# IMX477_MIPI_HDMI.net
KiCad netlist of a schematic drawn in Altium Designer
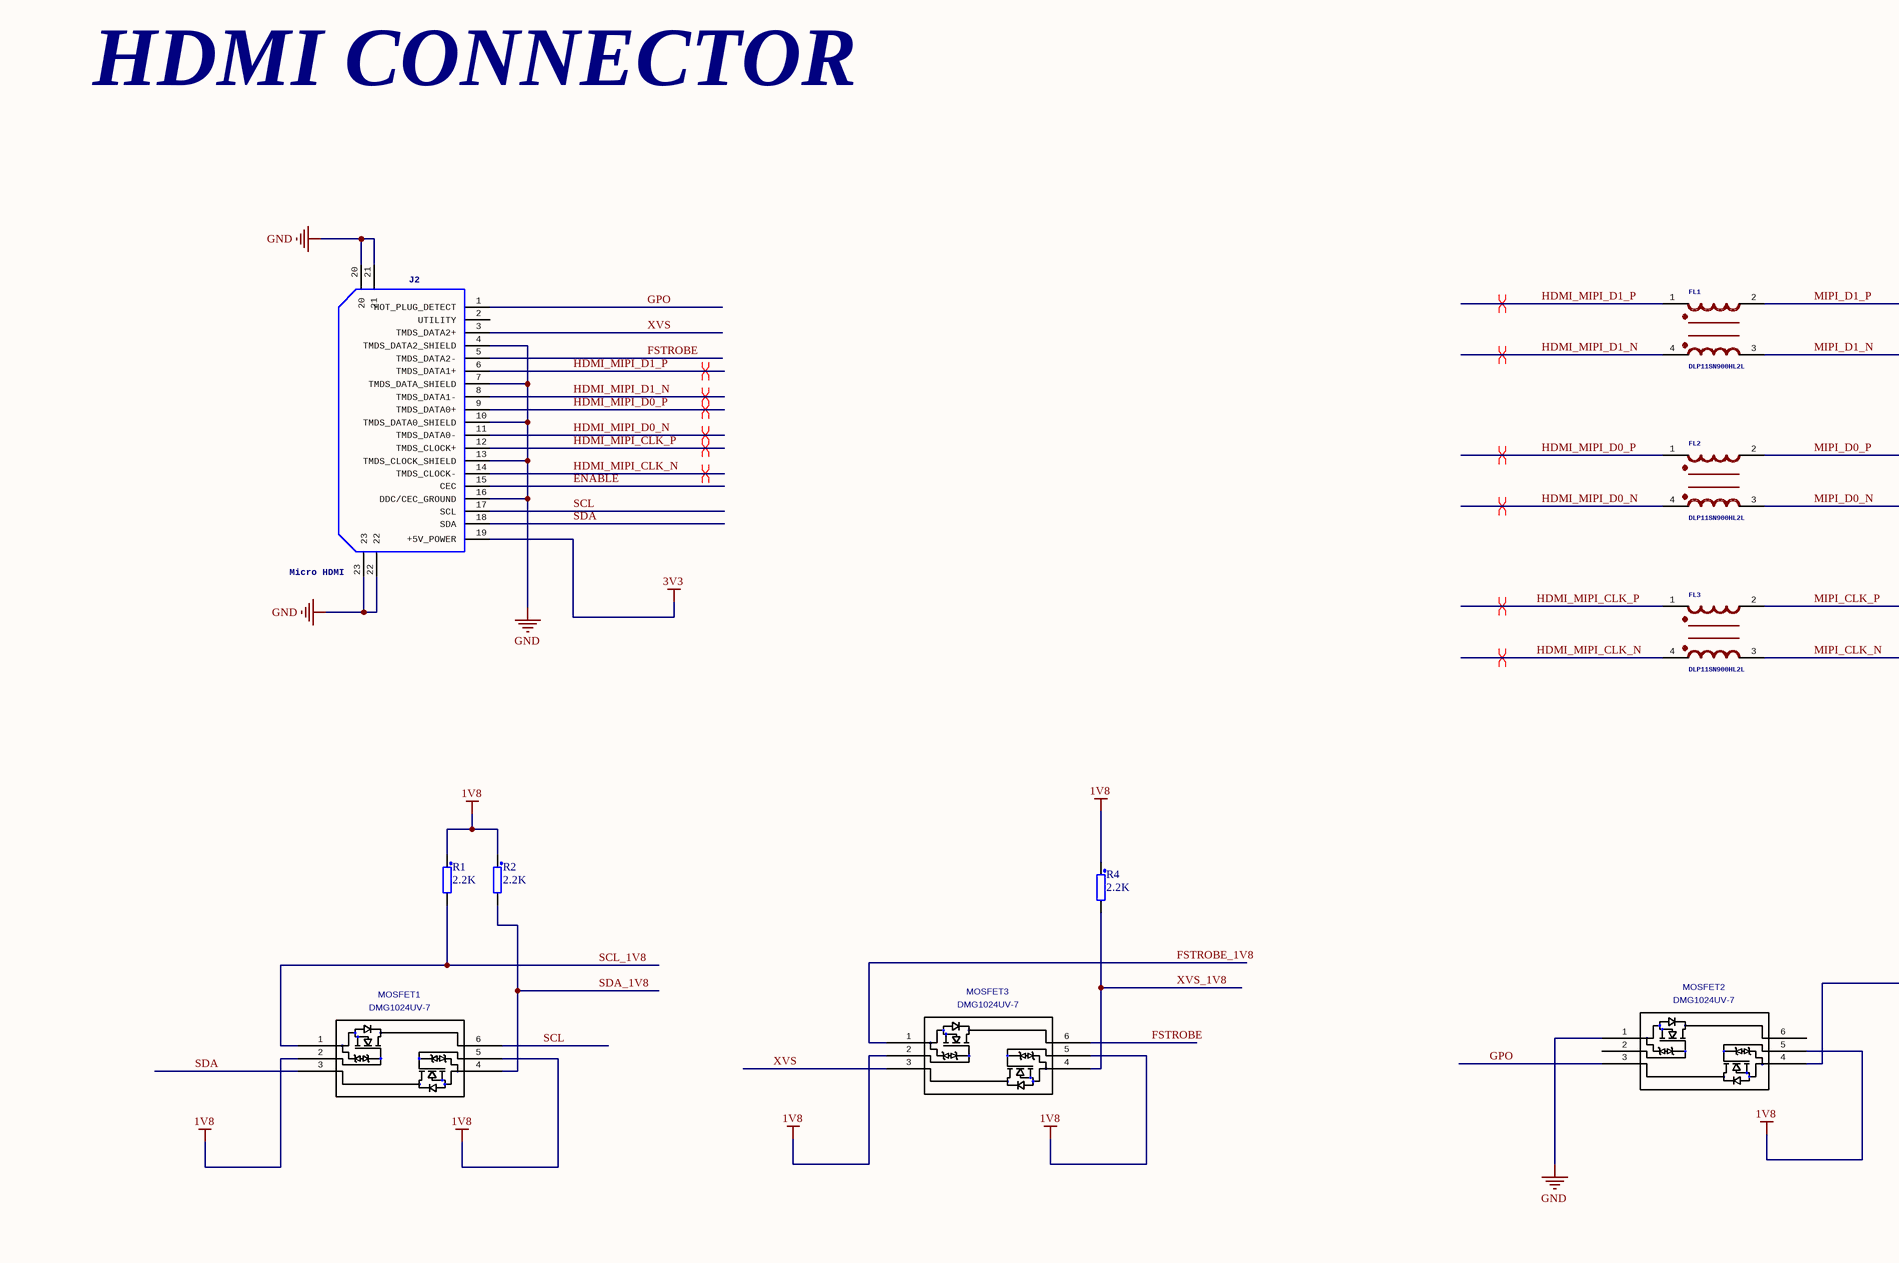
[diagram p0: IMX477_MIPI_HDMI.SchDoc, top left]
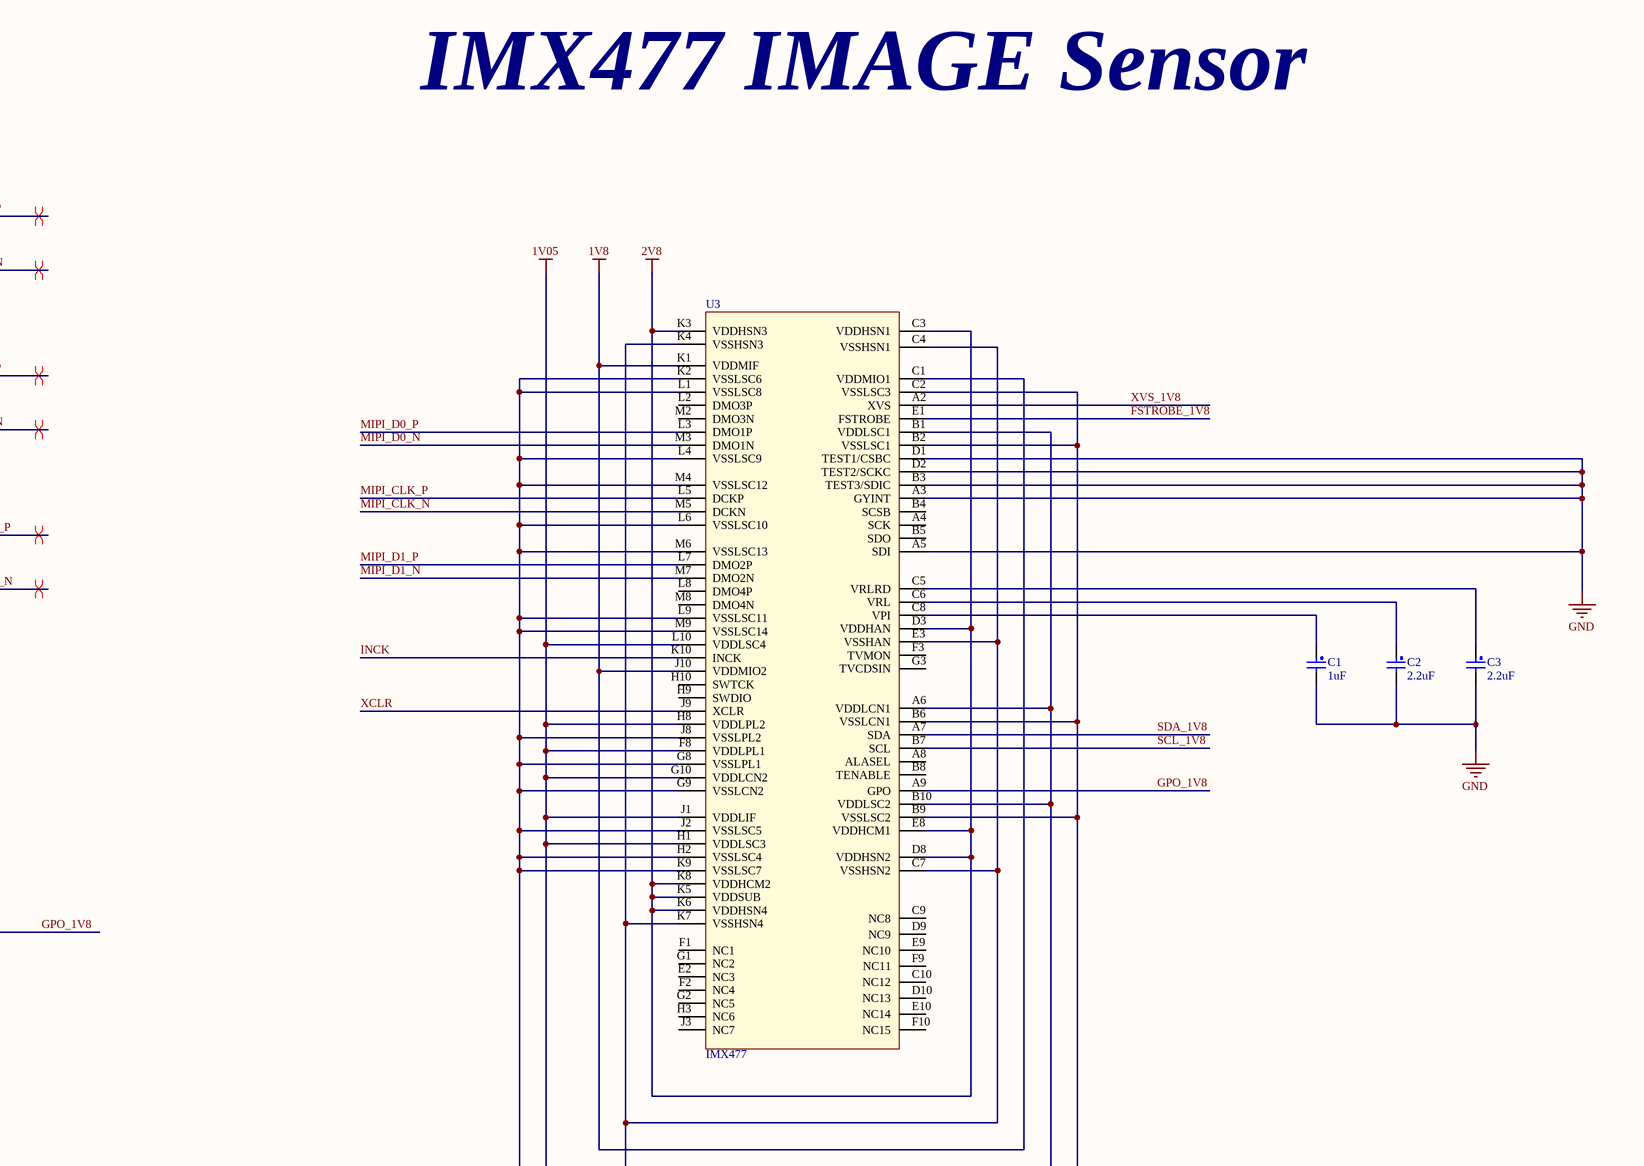
[diagram p1: IMX477_MIPI_HDMI.SchDoc, top right]
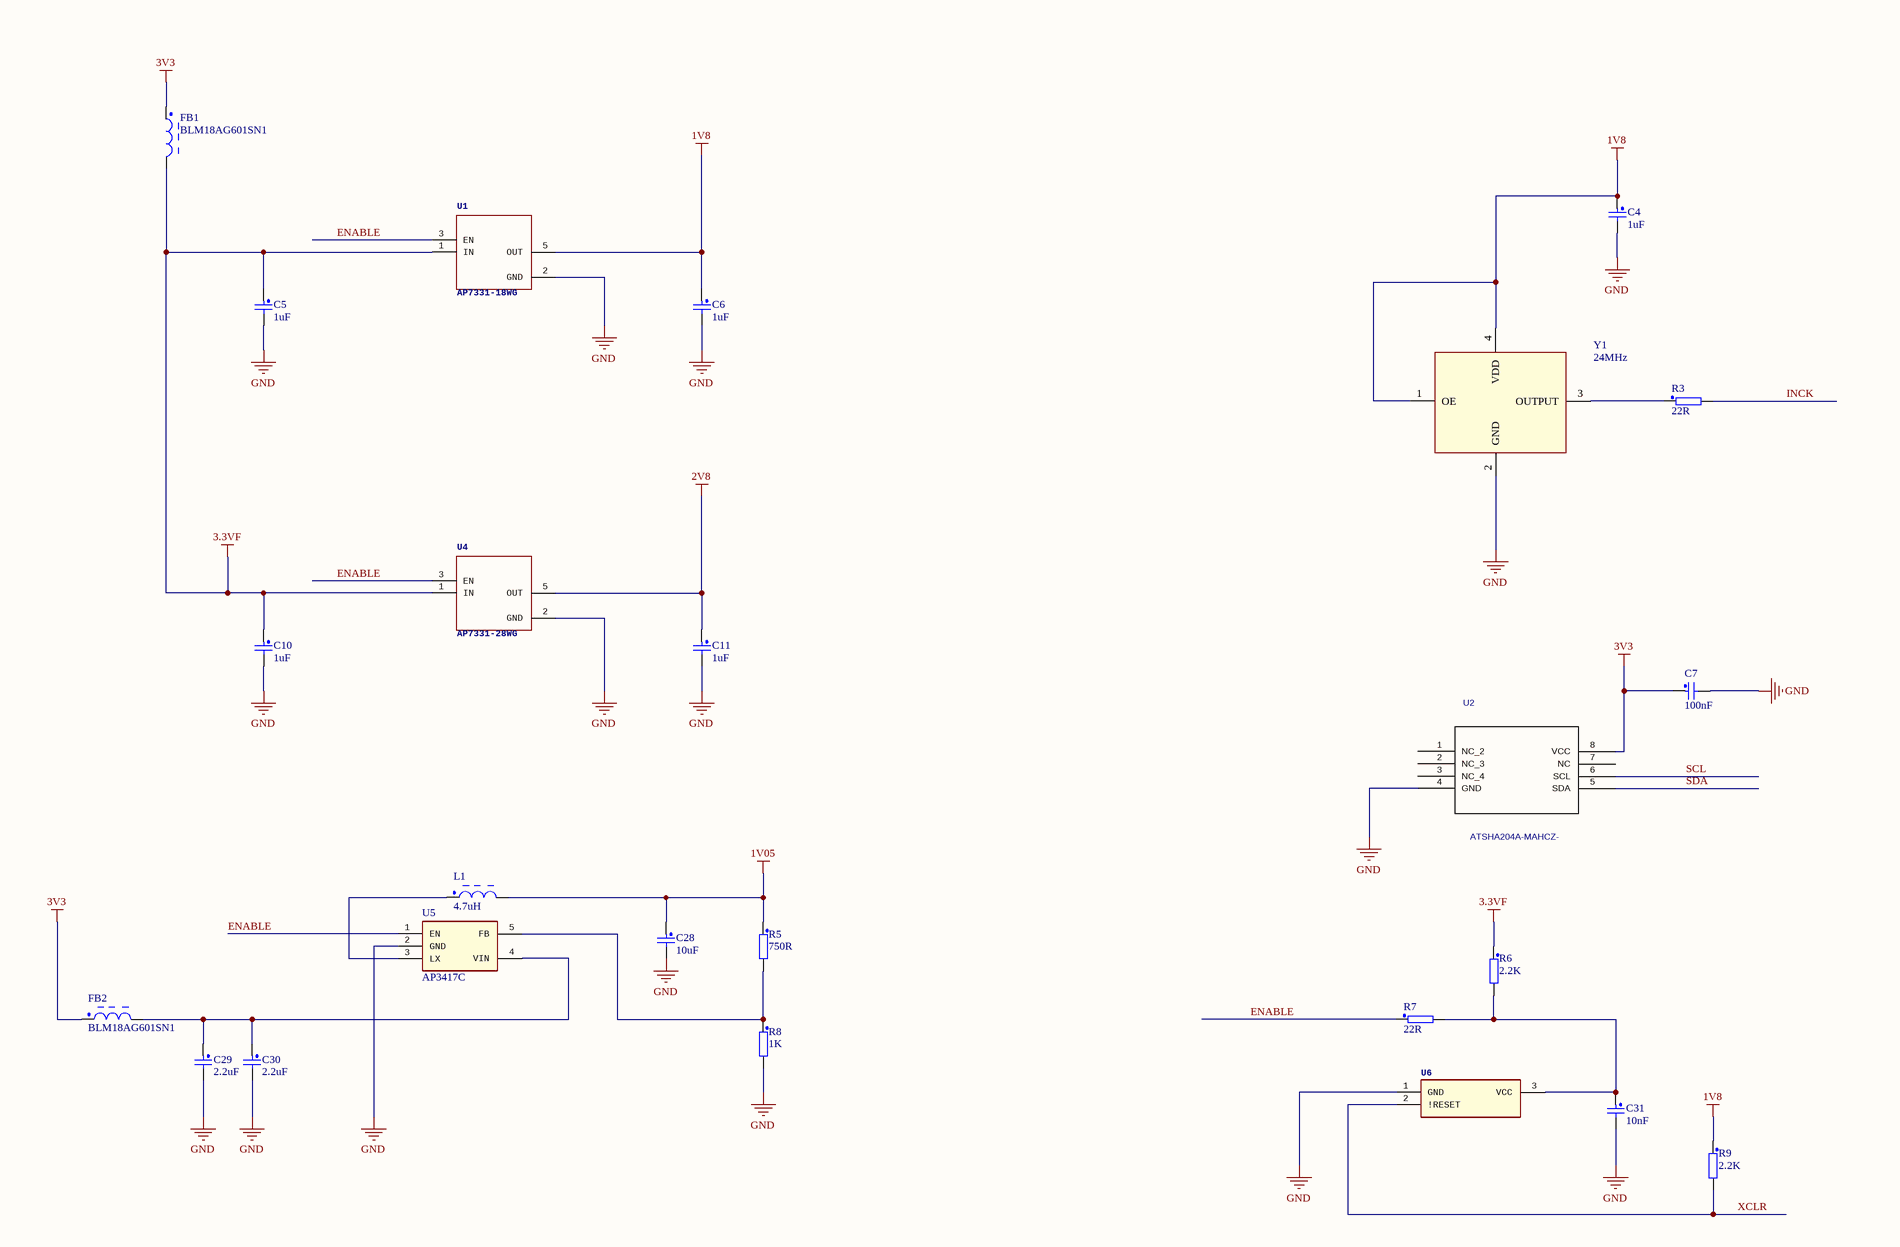
[diagram p2: IMX477_MIPI_HDMI.SchDoc, bottom left]
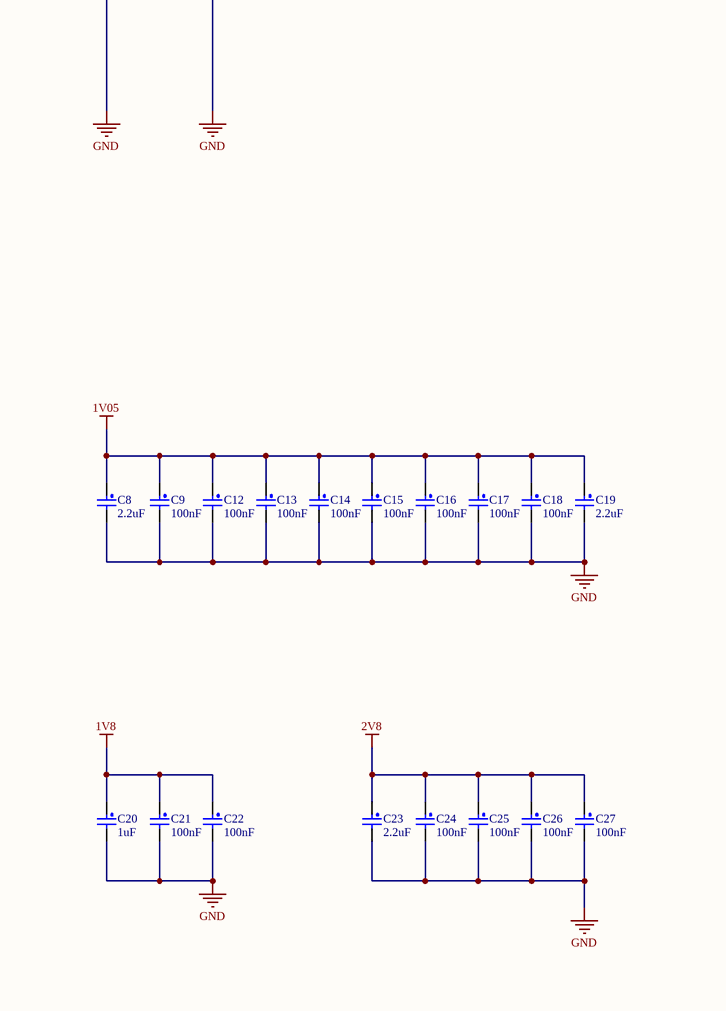
[diagram p3: IMX477_MIPI_HDMI.SchDoc, bottom right]

(export (version "E")
  (design (tool "Eeschema 10.0.6"))
  (components
    (comp (ref "C1")
      (value "1uF")
      (footprint "CAP-0402")
      (description "Capacitor")
      (libsource (lib "TASK-3DLIB") (part "CAP"))
    )
    (comp (ref "C2")
      (value "2.2uF")
      (footprint "CAP-0603")
      (description "Capacitor")
      (libsource (lib "TASK-3DLIB") (part "CAP"))
    )
    (comp (ref "C3")
      (value "2.2uF")
      (footprint "CAP-0603")
      (description "Capacitor")
      (libsource (lib "TASK-3DLIB") (part "CAP"))
    )
    (comp (ref "C4")
      (value "1uF")
      (footprint "CAP-0402")
      (description "Capacitor")
      (libsource (lib "TASK-3DLIB") (part "CAP"))
    )
    (comp (ref "C5")
      (value "1uF")
      (footprint "CAP-0402")
      (description "Capacitor")
      (libsource (lib "TASK-3DLIB") (part "CAP"))
    )
    (comp (ref "C6")
      (value "1uF")
      (footprint "CAP-0402")
      (description "Capacitor")
      (libsource (lib "TASK-3DLIB") (part "CAP"))
    )
    (comp (ref "C7")
      (value "100nF")
      (footprint "CAP-0402")
      (description "Capacitor")
      (libsource (lib "TASK-3DLIB") (part "CAP"))
    )
    (comp (ref "C8")
      (value "2.2uF")
      (footprint "CAP-0603")
      (description "Capacitor")
      (libsource (lib "TASK-3DLIB") (part "CAP"))
    )
    (comp (ref "C9")
      (value "100nF")
      (footprint "CAP-0402")
      (description "Capacitor")
      (libsource (lib "TASK-3DLIB") (part "CAP"))
    )
    (comp (ref "C10")
      (value "1uF")
      (footprint "CAP-0402")
      (description "Capacitor")
      (libsource (lib "TASK-3DLIB") (part "CAP"))
    )
    (comp (ref "C11")
      (value "1uF")
      (footprint "CAP-0402")
      (description "Capacitor")
      (libsource (lib "TASK-3DLIB") (part "CAP"))
    )
    (comp (ref "C12")
      (value "100nF")
      (footprint "CAP-0402")
      (description "Capacitor")
      (libsource (lib "TASK-3DLIB") (part "CAP"))
    )
    (comp (ref "C13")
      (value "100nF")
      (footprint "CAP-0402")
      (description "Capacitor")
      (libsource (lib "TASK-3DLIB") (part "CAP"))
    )
    (comp (ref "C14")
      (value "100nF")
      (footprint "CAP-0402")
      (description "Capacitor")
      (libsource (lib "TASK-3DLIB") (part "CAP"))
    )
    (comp (ref "C15")
      (value "100nF")
      (footprint "CAP-0402")
      (description "Capacitor")
      (libsource (lib "TASK-3DLIB") (part "CAP"))
    )
    (comp (ref "C16")
      (value "100nF")
      (footprint "CAP-0402")
      (description "Capacitor")
      (libsource (lib "TASK-3DLIB") (part "CAP"))
    )
    (comp (ref "C17")
      (value "100nF")
      (footprint "CAP-0402")
      (description "Capacitor")
      (libsource (lib "TASK-3DLIB") (part "CAP"))
    )
    (comp (ref "C18")
      (value "100nF")
      (footprint "CAP-0402")
      (description "Capacitor")
      (libsource (lib "TASK-3DLIB") (part "CAP"))
    )
    (comp (ref "C19")
      (value "2.2uF")
      (footprint "CAP-0603")
      (description "Capacitor")
      (libsource (lib "TASK-3DLIB") (part "CAP"))
    )
    (comp (ref "C20")
      (value "1uF")
      (footprint "CAP-0402")
      (description "Capacitor")
      (libsource (lib "TASK-3DLIB") (part "CAP"))
    )
    (comp (ref "C21")
      (value "100nF")
      (footprint "CAP-0402")
      (description "Capacitor")
      (libsource (lib "TASK-3DLIB") (part "CAP"))
    )
    (comp (ref "C22")
      (value "100nF")
      (footprint "CAP-0402")
      (description "Capacitor")
      (libsource (lib "TASK-3DLIB") (part "CAP"))
    )
    (comp (ref "C23")
      (value "2.2uF")
      (footprint "CAP-0603")
      (description "Capacitor")
      (libsource (lib "TASK-3DLIB") (part "CAP"))
    )
    (comp (ref "C24")
      (value "100nF")
      (footprint "CAP-0402")
      (description "Capacitor")
      (libsource (lib "TASK-3DLIB") (part "CAP"))
    )
    (comp (ref "C25")
      (value "100nF")
      (footprint "CAP-0402")
      (description "Capacitor")
      (libsource (lib "TASK-3DLIB") (part "CAP"))
    )
    (comp (ref "C26")
      (value "100nF")
      (footprint "CAP-0402")
      (description "Capacitor")
      (libsource (lib "TASK-3DLIB") (part "CAP"))
    )
    (comp (ref "C27")
      (value "100nF")
      (footprint "CAP-0402")
      (description "Capacitor")
      (libsource (lib "TASK-3DLIB") (part "CAP"))
    )
    (comp (ref "C28")
      (value "10uF")
      (footprint "CAP-0805-S")
      (description "Capacitor")
      (libsource (lib "TASK-3DLIB") (part "CAP"))
    )
    (comp (ref "C29")
      (value "2.2uF")
      (footprint "CAP-0603")
      (description "Capacitor")
      (libsource (lib "TASK-3DLIB") (part "CAP"))
    )
    (comp (ref "C30")
      (value "2.2uF")
      (footprint "CAP-0603")
      (description "Capacitor")
      (libsource (lib "TASK-3DLIB") (part "CAP"))
    )
    (comp (ref "C31")
      (value "10nF")
      (footprint "CAP-0402")
      (description "Capacitor")
      (libsource (lib "TASK-3DLIB") (part "CAP"))
    )
    (comp (ref "FB1")
      (value "BLM18AG601SN1")
      (footprint "FBD-0603-S")
      (description "Inductor")
      (libsource (lib "TASK-3DLIB") (part "INDUCTOR"))
    )
    (comp (ref "FB2")
      (value "BLM18AG601SN1")
      (footprint "FBD-0603-S")
      (description "Inductor")
      (libsource (lib "TASK-3DLIB") (part "INDUCTOR"))
    )
    (comp (ref "FL1")
      (value "DLP11SN900HL2L")
      (footprint "DLP11SN900HL2L")
      (fields (field (name "MF") "Murata") (field (name "DIGI-KEY_PART_NUMBER") "490-5143-1-ND"))
      (libsource (lib "TASK-3DLIB") (part "DLP11SN900HL2L"))
    )
    (comp (ref "FL2")
      (value "DLP11SN900HL2L")
      (footprint "DLP11SN900HL2L")
      (fields (field (name "MF") "Murata") (field (name "DIGI-KEY_PART_NUMBER") "490-5143-1-ND"))
      (libsource (lib "TASK-3DLIB") (part "DLP11SN900HL2L"))
    )
    (comp (ref "FL3")
      (value "DLP11SN900HL2L")
      (footprint "DLP11SN900HL2L")
      (fields (field (name "MF") "Murata") (field (name "DIGI-KEY_PART_NUMBER") "490-5143-1-ND"))
      (libsource (lib "TASK-3DLIB") (part "DLP11SN900HL2L"))
    )
    (comp (ref "J2")
      (value "Micro HDMI")
      (footprint "HDMI-0467650301")
      (fields (field (name "MANUFACTURER_PART_NUMBER") "0467650301"))
      (libsource (lib "TASK-3DLIB") (part "HDMI-0467650301"))
    )
    (comp (ref "L1")
      (value "4.7uH")
      (footprint "IND-1008")
      (description "Inductor")
      (libsource (lib "TASK-3DLIB") (part "INDUCTOR"))
    )
    (comp (ref "MOSFET1")
      (value "DMG1024UV-7")
      (footprint "SOT-563_DIO")
      (fields (field (name "COPYRIGHT") "Copyright (C) 2018 Accelerated Designs. All rights reserved"))
      (libsource (lib "TASK-3DLIB") (part "DMG1024UV-7"))
    )
    (comp (ref "MOSFET2")
      (value "DMG1024UV-7")
      (footprint "SOT-563_DIO")
      (fields (field (name "COPYRIGHT") "Copyright (C) 2018 Accelerated Designs. All rights reserved"))
      (libsource (lib "TASK-3DLIB") (part "DMG1024UV-7"))
    )
    (comp (ref "MOSFET3")
      (value "DMG1024UV-7")
      (footprint "SOT-563_DIO")
      (fields (field (name "COPYRIGHT") "Copyright (C) 2018 Accelerated Designs. All rights reserved"))
      (libsource (lib "TASK-3DLIB") (part "DMG1024UV-7"))
    )
    (comp (ref "R1") (value "2.2K") (footprint "RES-0402") (libsource (lib "TASK-3DLIB") (part "RES")))
    (comp (ref "R2") (value "2.2K") (footprint "RES-0402") (libsource (lib "TASK-3DLIB") (part "RES")))
    (comp (ref "R3") (value "22R") (footprint "RES-0402") (libsource (lib "TASK-3DLIB") (part "RES")))
    (comp (ref "R4") (value "2.2K") (footprint "RES-0402") (libsource (lib "TASK-3DLIB") (part "RES")))
    (comp (ref "R5") (value "750R") (footprint "RES-0402") (libsource (lib "TASK-3DLIB") (part "RES")))
    (comp (ref "R6") (value "2.2K") (footprint "RES-0402") (libsource (lib "TASK-3DLIB") (part "RES")))
    (comp (ref "R7") (value "22R") (footprint "RES-0402") (libsource (lib "TASK-3DLIB") (part "RES")))
    (comp (ref "R8") (value "1K") (footprint "RES-0402") (libsource (lib "TASK-3DLIB") (part "RES")))
    (comp (ref "R9") (value "2.2K") (footprint "RES-0402") (libsource (lib "TASK-3DLIB") (part "RES")))
    (comp (ref "U1")
      (value "AP7331-18WG")
      (footprint "AP7331-sot-25")
      (fields
        (field (name "MP") "AP7331-18WG-7")
        (field (name "MF") "Diodes Inc.")
        (field (name "DIGI-KEY_PART_NUMBER") "AP7331-18WG-7DICT-ND")
      )
      (libsource (lib "TASK-3DLIB") (part "AP7331-xxWG-7"))
    )
    (comp (ref "U2")
      (value "ATSHA204A-MAHCZ-")
      (footprint "ATSHA204A")
      (fields
        (field (name "MANUFACTURER_PART_NUMBER") "ATSHA204A-MAHCZ-T")
        (field (name "COPYRIGHT") "Copyright (C) 2018 Accelerated Designs. All rights reserved")
      )
      (libsource (lib "TASK-3DLIB") (part "ATSHA204A-MAHCZ-"))
    )
    (comp (ref "U3") (value "IMX477") (footprint "IMX477") (libsource (lib "TASK-3DLIB") (part "IMX477")))
    (comp (ref "U4")
      (value "AP7331-28WG")
      (footprint "AP7331-sot-25")
      (fields
        (field (name "MP") "AP7331-18WG-7")
        (field (name "MF") "Diodes Inc.")
        (field (name "DIGI-KEY_PART_NUMBER") "AP7331-18WG-7DICT-ND")
      )
      (libsource (lib "TASK-3DLIB") (part "AP7331-xxWG-7"))
    )
    (comp (ref "U5")
      (value "AP3417C")
      (footprint "SOT23-5-3D")
      (libsource (lib "TASK-3DLIB") (part "AP3417C"))
    )
    (comp (ref "U6")
      (value "~")
      (footprint "SOT96P240X110-3N")
      (fields
        (field (name "MANUFACTURER_PART_NUMBER") "APX803-29SAG-7")
        (field (name "MOUSER_PART_NUMBER") "621-APX803-29SAG-7")
      )
      (libsource (lib "TASK-3DLIB") (part "APX803-29SAG-7"))
    )
    (comp (ref "Y1") (value "24MHz") (footprint "3225-OSC") (libsource (lib "TASK-3DLIB") (part "OSC-3225")))
  )
  (nets
    (net (code "1") (name "/ENABLE") (class "Default")
      (node (ref "J2") (pin "15") (pinfunction "CEC_15") (pintype "passive"))
      (node (ref "R7") (pin "1") (pintype "passive"))
      (node (ref "U1") (pin "3") (pinfunction "EN_3") (pintype "passive"))
      (node (ref "U4") (pin "3") (pinfunction "EN_3") (pintype "passive"))
      (node (ref "U5") (pin "1") (pinfunction "EN_1") (pintype "passive"))
    )
    (net (code "2") (name "/FSTROBE") (class "Default")
      (node (ref "J2") (pin "5") (pinfunction "TMDS_DATA2-_5") (pintype "passive"))
      (node (ref "MOSFET3") (pin "6") (pinfunction "D2_6") (pintype "passive"))
    )
    (net (code "3") (name "/FSTROBE_1V8") (class "Default")
      (node (ref "MOSFET3") (pin "1") (pinfunction "S2_1") (pintype "passive"))
      (node (ref "U3") (pin "E1") (pinfunction "FSTROBE_E1") (pintype "passive"))
    )
    (net (code "4") (name "/GPO") (class "Default")
      (node (ref "J2") (pin "1") (pinfunction "HOT_PLUG_DETECT_1") (pintype "passive"))
      (node (ref "MOSFET2") (pin "3") (pinfunction "D1_3") (pintype "passive"))
    )
    (net (code "5") (name "/GPO_1V8") (class "Default")
      (node (ref "MOSFET2") (pin "4") (pinfunction "S1_4") (pintype "passive"))
      (node (ref "U3") (pin "A9") (pinfunction "GPO_A9") (pintype "passive"))
    )
    (net (code "6") (name "/HDMI_MIPI_CLK_N") (class "Default")
      (node (ref "FL3") (pin "4") (pinfunction "4_4") (pintype "passive"))
      (node (ref "J2") (pin "14") (pinfunction "TMDS_CLOCK-_14") (pintype "passive"))
    )
    (net (code "7") (name "/HDMI_MIPI_CLK_P") (class "Default")
      (node (ref "FL3") (pin "1") (pinfunction "1_1") (pintype "passive"))
      (node (ref "J2") (pin "12") (pinfunction "TMDS_CLOCK+_12") (pintype "passive"))
    )
    (net (code "8") (name "/HDMI_MIPI_D0_N") (class "Default")
      (node (ref "FL2") (pin "4") (pinfunction "4_4") (pintype "passive"))
      (node (ref "J2") (pin "11") (pinfunction "TMDS_DATA0-_11") (pintype "passive"))
    )
    (net (code "9") (name "/HDMI_MIPI_D0_P") (class "Default")
      (node (ref "FL2") (pin "1") (pinfunction "1_1") (pintype "passive"))
      (node (ref "J2") (pin "9") (pinfunction "TMDS_DATA0+_9") (pintype "passive"))
    )
    (net (code "10") (name "/HDMI_MIPI_D1_N") (class "Default")
      (node (ref "FL1") (pin "4") (pinfunction "4_4") (pintype "passive"))
      (node (ref "J2") (pin "8") (pinfunction "TMDS_DATA1-_8") (pintype "passive"))
    )
    (net (code "11") (name "/HDMI_MIPI_D1_P") (class "Default")
      (node (ref "FL1") (pin "1") (pinfunction "1_1") (pintype "passive"))
      (node (ref "J2") (pin "6") (pinfunction "TMDS_DATA1+_6") (pintype "passive"))
    )
    (net (code "12") (name "/INCK") (class "Default")
      (node (ref "R3") (pin "2") (pintype "passive"))
      (node (ref "U3") (pin "K10") (pinfunction "INCK_K10") (pintype "passive"))
    )
    (net (code "13") (name "/MIPI_CLK_N") (class "Default")
      (node (ref "FL3") (pin "3") (pinfunction "3_3") (pintype "passive"))
      (node (ref "U3") (pin "M5") (pinfunction "DCKN_M5") (pintype "passive"))
    )
    (net (code "14") (name "/MIPI_CLK_P") (class "Default")
      (node (ref "FL3") (pin "2") (pinfunction "2_2") (pintype "passive"))
      (node (ref "U3") (pin "L5") (pinfunction "DCKP_L5") (pintype "passive"))
    )
    (net (code "15") (name "/MIPI_D0_N") (class "Default")
      (node (ref "FL2") (pin "3") (pinfunction "3_3") (pintype "passive"))
      (node (ref "U3") (pin "M3") (pinfunction "DMO1N_M3") (pintype "passive"))
    )
    (net (code "16") (name "/MIPI_D0_P") (class "Default")
      (node (ref "FL2") (pin "2") (pinfunction "2_2") (pintype "passive"))
      (node (ref "U3") (pin "L3") (pinfunction "DMO1P_L3") (pintype "passive"))
    )
    (net (code "17") (name "/MIPI_D1_N") (class "Default")
      (node (ref "FL1") (pin "3") (pinfunction "3_3") (pintype "passive"))
      (node (ref "U3") (pin "M7") (pinfunction "DMO2N_M7") (pintype "passive"))
    )
    (net (code "18") (name "/MIPI_D1_P") (class "Default")
      (node (ref "FL1") (pin "2") (pinfunction "2_2") (pintype "passive"))
      (node (ref "U3") (pin "L7") (pinfunction "DMO2P_L7") (pintype "passive"))
    )
    (net (code "19") (name "/SCL") (class "Default")
      (node (ref "J2") (pin "17") (pinfunction "SCL_17") (pintype "passive"))
      (node (ref "MOSFET1") (pin "6") (pinfunction "D2_6") (pintype "passive"))
      (node (ref "U2") (pin "6") (pinfunction "SCL_6") (pintype "passive"))
    )
    (net (code "20") (name "/SCL_1V8") (class "Default")
      (node (ref "MOSFET1") (pin "1") (pinfunction "S2_1") (pintype "passive"))
      (node (ref "R1") (pin "2") (pintype "passive"))
      (node (ref "U3") (pin "B7") (pinfunction "SCL_B7") (pintype "passive"))
    )
    (net (code "21") (name "/SDA") (class "Default")
      (node (ref "J2") (pin "18") (pinfunction "SDA_18") (pintype "passive"))
      (node (ref "MOSFET1") (pin "3") (pinfunction "D1_3") (pintype "passive"))
      (node (ref "U2") (pin "5") (pinfunction "SDA_5") (pintype "passive"))
    )
    (net (code "22") (name "/SDA_1V8") (class "Default")
      (node (ref "MOSFET1") (pin "4") (pinfunction "S1_4") (pintype "passive"))
      (node (ref "R2") (pin "2") (pintype "passive"))
      (node (ref "U3") (pin "A7") (pinfunction "SDA_A7") (pintype "passive"))
    )
    (net (code "23") (name "/XCLR") (class "Default")
      (node (ref "R9") (pin "2") (pintype "passive"))
      (node (ref "U3") (pin "J9") (pinfunction "XCLR_J9") (pintype "passive"))
      (node (ref "U6") (pin "2") (pinfunction "!RESET_2") (pintype "passive"))
    )
    (net (code "24") (name "/XVS") (class "Default")
      (node (ref "J2") (pin "3") (pinfunction "TMDS_DATA2+_3") (pintype "passive"))
      (node (ref "MOSFET3") (pin "3") (pinfunction "D1_3") (pintype "passive"))
    )
    (net (code "25") (name "/XVS_1V8") (class "Default")
      (node (ref "MOSFET3") (pin "4") (pinfunction "S1_4") (pintype "passive"))
      (node (ref "R4") (pin "2") (pintype "passive"))
      (node (ref "U3") (pin "A2") (pinfunction "XVS_A2") (pintype "passive"))
    )
    (net (code "26") (name "1V05") (class "Default")
      (node (ref "C12") (pin "1") (pinfunction "1_1") (pintype "passive"))
      (node (ref "C13") (pin "1") (pinfunction "1_1") (pintype "passive"))
      (node (ref "C14") (pin "1") (pinfunction "1_1") (pintype "passive"))
      (node (ref "C15") (pin "1") (pinfunction "1_1") (pintype "passive"))
      (node (ref "C16") (pin "1") (pinfunction "1_1") (pintype "passive"))
      (node (ref "C17") (pin "1") (pinfunction "1_1") (pintype "passive"))
      (node (ref "C18") (pin "1") (pinfunction "1_1") (pintype "passive"))
      (node (ref "C19") (pin "1") (pinfunction "1_1") (pintype "passive"))
      (node (ref "C28") (pin "1") (pinfunction "1_1") (pintype "passive"))
      (node (ref "C8") (pin "1") (pinfunction "1_1") (pintype "passive"))
      (node (ref "C9") (pin "1") (pinfunction "1_1") (pintype "passive"))
      (node (ref "L1") (pin "2") (pinfunction "2_2") (pintype "passive"))
      (node (ref "R5") (pin "1") (pintype "passive"))
      (node (ref "U3") (pin "A6") (pinfunction "VDDLCN1_A6") (pintype "passive"))
      (node (ref "U3") (pin "B1") (pinfunction "VDDLSC1_B1") (pintype "passive"))
      (node (ref "U3") (pin "B10") (pinfunction "VDDLSC2_B10") (pintype "passive"))
      (node (ref "U3") (pin "F8") (pinfunction "VDDLPL1_F8") (pintype "passive"))
      (node (ref "U3") (pin "G10") (pinfunction "VDDLCN2_G10") (pintype "passive"))
      (node (ref "U3") (pin "H1") (pinfunction "VDDLSC3_H1") (pintype "passive"))
      (node (ref "U3") (pin "H8") (pinfunction "VDDLPL2_H8") (pintype "passive"))
      (node (ref "U3") (pin "J1") (pinfunction "VDDLIF_J1") (pintype "passive"))
      (node (ref "U3") (pin "L10") (pinfunction "VDDLSC4_L10") (pintype "passive"))
    )
    (net (code "27") (name "1V8") (class "Default")
      (node (ref "C20") (pin "1") (pinfunction "1_1") (pintype "passive"))
      (node (ref "C21") (pin "1") (pinfunction "1_1") (pintype "passive"))
      (node (ref "C22") (pin "1") (pinfunction "1_1") (pintype "passive"))
      (node (ref "C4") (pin "1") (pinfunction "1_1") (pintype "passive"))
      (node (ref "C6") (pin "1") (pinfunction "1_1") (pintype "passive"))
      (node (ref "MOSFET1") (pin "2") (pinfunction "G2_2") (pintype "passive"))
      (node (ref "MOSFET1") (pin "5") (pinfunction "G1_5") (pintype "passive"))
      (node (ref "MOSFET2") (pin "5") (pinfunction "G1_5") (pintype "passive"))
      (node (ref "MOSFET3") (pin "2") (pinfunction "G2_2") (pintype "passive"))
      (node (ref "MOSFET3") (pin "5") (pinfunction "G1_5") (pintype "passive"))
      (node (ref "R1") (pin "1") (pintype "passive"))
      (node (ref "R2") (pin "1") (pintype "passive"))
      (node (ref "R4") (pin "1") (pintype "passive"))
      (node (ref "R9") (pin "1") (pintype "passive"))
      (node (ref "U1") (pin "5") (pinfunction "OUT_5") (pintype "passive"))
      (node (ref "U3") (pin "C1") (pinfunction "VDDMIO1_C1") (pintype "passive"))
      (node (ref "U3") (pin "J10") (pinfunction "VDDMIO2_J10") (pintype "passive"))
      (node (ref "U3") (pin "K1") (pinfunction "VDDMIF_K1") (pintype "passive"))
      (node (ref "Y1") (pin "1") (pinfunction "OE_1") (pintype "passive"))
      (node (ref "Y1") (pin "4") (pinfunction "VDD_4") (pintype "passive"))
    )
    (net (code "28") (name "2V8") (class "Default")
      (node (ref "C11") (pin "1") (pinfunction "1_1") (pintype "passive"))
      (node (ref "C23") (pin "1") (pinfunction "1_1") (pintype "passive"))
      (node (ref "C24") (pin "1") (pinfunction "1_1") (pintype "passive"))
      (node (ref "C25") (pin "1") (pinfunction "1_1") (pintype "passive"))
      (node (ref "C26") (pin "1") (pinfunction "1_1") (pintype "passive"))
      (node (ref "C27") (pin "1") (pinfunction "1_1") (pintype "passive"))
      (node (ref "U3") (pin "C3") (pinfunction "VDDHSN1_C3") (pintype "passive"))
      (node (ref "U3") (pin "D3") (pinfunction "VDDHAN_D3") (pintype "passive"))
      (node (ref "U3") (pin "D8") (pinfunction "VDDHSN2_D8") (pintype "passive"))
      (node (ref "U3") (pin "E8") (pinfunction "VDDHCM1_E8") (pintype "passive"))
      (node (ref "U3") (pin "K3") (pinfunction "VDDHSN3_K3") (pintype "passive"))
      (node (ref "U3") (pin "K5") (pinfunction "VDDSUB_K5") (pintype "passive"))
      (node (ref "U3") (pin "K6") (pinfunction "VDDHSN4_K6") (pintype "passive"))
      (node (ref "U3") (pin "K8") (pinfunction "VDDHCM2_K8") (pintype "passive"))
      (node (ref "U4") (pin "5") (pinfunction "OUT_5") (pintype "passive"))
    )
    (net (code "29") (name "3.3VF") (class "Default")
      (node (ref "C10") (pin "1") (pinfunction "1_1") (pintype "passive"))
      (node (ref "C5") (pin "1") (pinfunction "1_1") (pintype "passive"))
      (node (ref "FB1") (pin "2") (pinfunction "2_2") (pintype "passive"))
      (node (ref "R6") (pin "1") (pintype "passive"))
      (node (ref "U1") (pin "1") (pinfunction "IN_1") (pintype "passive"))
      (node (ref "U4") (pin "1") (pinfunction "IN_1") (pintype "passive"))
    )
    (net (code "30") (name "3V3") (class "Default")
      (node (ref "C7") (pin "1") (pinfunction "1_1") (pintype "passive"))
      (node (ref "FB1") (pin "1") (pinfunction "1_1") (pintype "passive"))
      (node (ref "FB2") (pin "1") (pinfunction "1_1") (pintype "passive"))
      (node (ref "J2") (pin "19") (pinfunction "+5V_POWER_19") (pintype "passive"))
      (node (ref "U2") (pin "8") (pinfunction "VCC_8") (pintype "power_in"))
    )
    (net (code "31") (name "GND") (class "Default")
      (node (ref "C1") (pin "2") (pinfunction "2_2") (pintype "passive"))
      (node (ref "C10") (pin "2") (pinfunction "2_2") (pintype "passive"))
      (node (ref "C11") (pin "2") (pinfunction "2_2") (pintype "passive"))
      (node (ref "C12") (pin "2") (pinfunction "2_2") (pintype "passive"))
      (node (ref "C13") (pin "2") (pinfunction "2_2") (pintype "passive"))
      (node (ref "C14") (pin "2") (pinfunction "2_2") (pintype "passive"))
      (node (ref "C15") (pin "2") (pinfunction "2_2") (pintype "passive"))
      (node (ref "C16") (pin "2") (pinfunction "2_2") (pintype "passive"))
      (node (ref "C17") (pin "2") (pinfunction "2_2") (pintype "passive"))
      (node (ref "C18") (pin "2") (pinfunction "2_2") (pintype "passive"))
      (node (ref "C19") (pin "2") (pinfunction "2_2") (pintype "passive"))
      (node (ref "C2") (pin "2") (pinfunction "2_2") (pintype "passive"))
      (node (ref "C20") (pin "2") (pinfunction "2_2") (pintype "passive"))
      (node (ref "C21") (pin "2") (pinfunction "2_2") (pintype "passive"))
      (node (ref "C22") (pin "2") (pinfunction "2_2") (pintype "passive"))
      (node (ref "C23") (pin "2") (pinfunction "2_2") (pintype "passive"))
      (node (ref "C24") (pin "2") (pinfunction "2_2") (pintype "passive"))
      (node (ref "C25") (pin "2") (pinfunction "2_2") (pintype "passive"))
      (node (ref "C26") (pin "2") (pinfunction "2_2") (pintype "passive"))
      (node (ref "C27") (pin "2") (pinfunction "2_2") (pintype "passive"))
      (node (ref "C28") (pin "2") (pinfunction "2_2") (pintype "passive"))
      (node (ref "C29") (pin "2") (pinfunction "2_2") (pintype "passive"))
      (node (ref "C3") (pin "2") (pinfunction "2_2") (pintype "passive"))
      (node (ref "C30") (pin "2") (pinfunction "2_2") (pintype "passive"))
      (node (ref "C31") (pin "2") (pinfunction "2_2") (pintype "passive"))
      (node (ref "C4") (pin "2") (pinfunction "2_2") (pintype "passive"))
      (node (ref "C5") (pin "2") (pinfunction "2_2") (pintype "passive"))
      (node (ref "C6") (pin "2") (pinfunction "2_2") (pintype "passive"))
      (node (ref "C7") (pin "2") (pinfunction "2_2") (pintype "passive"))
      (node (ref "C8") (pin "2") (pinfunction "2_2") (pintype "passive"))
      (node (ref "C9") (pin "2") (pinfunction "2_2") (pintype "passive"))
      (node (ref "J2") (pin "10") (pinfunction "TMDS_DATA0_SHIELD_10") (pintype "passive"))
      (node (ref "J2") (pin "13") (pinfunction "TMDS_CLOCK_SHIELD_13") (pintype "passive"))
      (node (ref "J2") (pin "16") (pinfunction "DDC/CEC_GROUND_16") (pintype "passive"))
      (node (ref "J2") (pin "20") (pinfunction "20_20") (pintype "passive"))
      (node (ref "J2") (pin "21") (pinfunction "21_21") (pintype "passive"))
      (node (ref "J2") (pin "22") (pinfunction "22_22") (pintype "passive"))
      (node (ref "J2") (pin "23") (pinfunction "23_23") (pintype "passive"))
      (node (ref "J2") (pin "4") (pinfunction "TMDS_DATA2_SHIELD_4") (pintype "passive"))
      (node (ref "J2") (pin "7") (pinfunction "TMDS_DATA_SHIELD_7") (pintype "passive"))
      (node (ref "MOSFET2") (pin "1") (pinfunction "S2_1") (pintype "passive"))
      (node (ref "R8") (pin "2") (pintype "passive"))
      (node (ref "U1") (pin "2") (pinfunction "GND_2") (pintype "power_in"))
      (node (ref "U2") (pin "4") (pinfunction "GND_4") (pintype "power_in"))
      (node (ref "U3") (pin "A3") (pinfunction "GYINT_A3") (pintype "passive"))
      (node (ref "U3") (pin "A5") (pinfunction "SDI_A5") (pintype "passive"))
      (node (ref "U3") (pin "B2") (pinfunction "VSSLSC1_B2") (pintype "passive"))
      (node (ref "U3") (pin "B3") (pinfunction "TEST3/SDIC_B3") (pintype "passive"))
      (node (ref "U3") (pin "B6") (pinfunction "VSSLCN1_B6") (pintype "passive"))
      (node (ref "U3") (pin "B9") (pinfunction "VSSLSC2_B9") (pintype "passive"))
      (node (ref "U3") (pin "C2") (pinfunction "VSSLSC3_C2") (pintype "passive"))
      (node (ref "U3") (pin "C4") (pinfunction "VSSHSN1_C4") (pintype "passive"))
      (node (ref "U3") (pin "C7") (pinfunction "VSSHSN2_C7") (pintype "passive"))
      (node (ref "U3") (pin "D1") (pinfunction "TEST1/CSBC_D1") (pintype "passive"))
      (node (ref "U3") (pin "D2") (pinfunction "TEST2/SCKC_D2") (pintype "passive"))
      (node (ref "U3") (pin "E3") (pinfunction "VSSHAN_E3") (pintype "passive"))
      (node (ref "U3") (pin "G8") (pinfunction "VSSLPL1_G8") (pintype "passive"))
      (node (ref "U3") (pin "G9") (pinfunction "VSSLCN2_G9") (pintype "passive"))
      (node (ref "U3") (pin "H2") (pinfunction "VSSLSC4_H2") (pintype "passive"))
      (node (ref "U3") (pin "J2") (pinfunction "VSSLSC5_J2") (pintype "passive"))
      (node (ref "U3") (pin "J8") (pinfunction "VSSLPL2_J8") (pintype "passive"))
      (node (ref "U3") (pin "K2") (pinfunction "VSSLSC6_K2") (pintype "passive"))
      (node (ref "U3") (pin "K4") (pinfunction "VSSHSN3_K4") (pintype "passive"))
      (node (ref "U3") (pin "K7") (pinfunction "VSSHSN4_K7") (pintype "passive"))
      (node (ref "U3") (pin "K9") (pinfunction "VSSLSC7_K9") (pintype "passive"))
      (node (ref "U3") (pin "L1") (pinfunction "VSSLSC8_L1") (pintype "passive"))
      (node (ref "U3") (pin "L4") (pinfunction "VSSLSC9_L4") (pintype "passive"))
      (node (ref "U3") (pin "L6") (pinfunction "VSSLSC10_L6") (pintype "passive"))
      (node (ref "U3") (pin "L9") (pinfunction "VSSLSC11_L9") (pintype "passive"))
      (node (ref "U3") (pin "M4") (pinfunction "VSSLSC12_M4") (pintype "passive"))
      (node (ref "U3") (pin "M6") (pinfunction "VSSLSC13_M6") (pintype "passive"))
      (node (ref "U3") (pin "M9") (pinfunction "VSSLSC14_M9") (pintype "passive"))
      (node (ref "U4") (pin "2") (pinfunction "GND_2") (pintype "power_in"))
      (node (ref "U5") (pin "2") (pinfunction "GND_2") (pintype "passive"))
      (node (ref "U6") (pin "1") (pinfunction "GND_1") (pintype "passive"))
      (node (ref "Y1") (pin "2") (pinfunction "GND_2") (pintype "passive"))
    )
    (net (code "32") (name "Net-(U3-VPI)") (class "Default")
      (node (ref "C1") (pin "1") (pinfunction "1_1") (pintype "passive"))
      (node (ref "U3") (pin "C8") (pinfunction "VPI_C8") (pintype "passive"))
    )
    (net (code "33") (name "Net-(U3-VRL)") (class "Default")
      (node (ref "C2") (pin "1") (pinfunction "1_1") (pintype "passive"))
      (node (ref "U3") (pin "C6") (pinfunction "VRL_C6") (pintype "passive"))
    )
    (net (code "34") (name "Net-(U3-VRLRD)") (class "Default")
      (node (ref "C3") (pin "1") (pinfunction "1_1") (pintype "passive"))
      (node (ref "U3") (pin "C5") (pinfunction "VRLRD_C5") (pintype "passive"))
    )
    (net (code "35") (name "Net-(U5-FB)") (class "Default")
      (node (ref "R5") (pin "2") (pintype "passive"))
      (node (ref "R8") (pin "1") (pintype "passive"))
      (node (ref "U5") (pin "5") (pinfunction "FB_5") (pintype "passive"))
    )
    (net (code "36") (name "Net-(U5-LX)") (class "Default")
      (node (ref "L1") (pin "1") (pinfunction "1_1") (pintype "passive"))
      (node (ref "U5") (pin "3") (pinfunction "LX_3") (pintype "passive"))
    )
    (net (code "37") (name "Net-(U5-VIN)") (class "Default")
      (node (ref "C29") (pin "1") (pinfunction "1_1") (pintype "passive"))
      (node (ref "C30") (pin "1") (pinfunction "1_1") (pintype "passive"))
      (node (ref "FB2") (pin "2") (pinfunction "2_2") (pintype "passive"))
      (node (ref "U5") (pin "4") (pinfunction "VIN_4") (pintype "passive"))
    )
    (net (code "38") (name "Net-(U6-VCC)") (class "Default")
      (node (ref "C31") (pin "1") (pinfunction "1_1") (pintype "passive"))
      (node (ref "R6") (pin "2") (pintype "passive"))
      (node (ref "R7") (pin "2") (pintype "passive"))
      (node (ref "U6") (pin "3") (pinfunction "VCC_3") (pintype "passive"))
    )
    (net (code "39") (name "Net-(Y1-OUTPUT)") (class "Default")
      (node (ref "R3") (pin "1") (pintype "passive"))
      (node (ref "Y1") (pin "3") (pinfunction "OUTPUT_3") (pintype "passive"))
    )
    (net (code "40") (name "unconnected-(J2-UTILITY-Pad2)") (class "Default")
      (node (ref "J2") (pin "2") (pinfunction "UTILITY_2") (pintype "passive"))
    )
    (net (code "41") (name "unconnected-(MOSFET2-D2-Pad6)") (class "Default")
      (node (ref "MOSFET2") (pin "6") (pinfunction "D2_6") (pintype "passive"))
    )
    (net (code "42") (name "unconnected-(MOSFET2-G2-Pad2)") (class "Default")
      (node (ref "MOSFET2") (pin "2") (pinfunction "G2_2") (pintype "passive"))
    )
    (net (code "43") (name "unconnected-(U2-NC-Pad7)") (class "Default")
      (node (ref "U2") (pin "7") (pinfunction "NC_7") (pintype "passive"))
    )
    (net (code "44") (name "unconnected-(U2-NC_2-Pad1)") (class "Default")
      (node (ref "U2") (pin "1") (pinfunction "NC_2_1") (pintype "passive"))
    )
    (net (code "45") (name "unconnected-(U2-NC_3-Pad2)") (class "Default")
      (node (ref "U2") (pin "2") (pinfunction "NC_3_2") (pintype "passive"))
    )
    (net (code "46") (name "unconnected-(U2-NC_4-Pad3)") (class "Default")
      (node (ref "U2") (pin "3") (pinfunction "NC_4_3") (pintype "passive"))
    )
    (net (code "47") (name "unconnected-(U3-ALASEL-PadA8)") (class "Default")
      (node (ref "U3") (pin "A8") (pinfunction "ALASEL_A8") (pintype "passive"))
    )
    (net (code "48") (name "unconnected-(U3-DMO3N-PadM2)") (class "Default")
      (node (ref "U3") (pin "M2") (pinfunction "DMO3N_M2") (pintype "passive"))
    )
    (net (code "49") (name "unconnected-(U3-DMO3P-PadL2)") (class "Default")
      (node (ref "U3") (pin "L2") (pinfunction "DMO3P_L2") (pintype "passive"))
    )
    (net (code "50") (name "unconnected-(U3-DMO4N-PadM8)") (class "Default")
      (node (ref "U3") (pin "M8") (pinfunction "DMO4N_M8") (pintype "passive"))
    )
    (net (code "51") (name "unconnected-(U3-DMO4P-PadL8)") (class "Default")
      (node (ref "U3") (pin "L8") (pinfunction "DMO4P_L8") (pintype "passive"))
    )
    (net (code "52") (name "unconnected-(U3-NC1-PadF1)") (class "Default")
      (node (ref "U3") (pin "F1") (pinfunction "NC1_F1") (pintype "passive"))
    )
    (net (code "53") (name "unconnected-(U3-NC2-PadG1)") (class "Default")
      (node (ref "U3") (pin "G1") (pinfunction "NC2_G1") (pintype "passive"))
    )
    (net (code "54") (name "unconnected-(U3-NC3-PadE2)") (class "Default")
      (node (ref "U3") (pin "E2") (pinfunction "NC3_E2") (pintype "passive"))
    )
    (net (code "55") (name "unconnected-(U3-NC4-PadF2)") (class "Default")
      (node (ref "U3") (pin "F2") (pinfunction "NC4_F2") (pintype "passive"))
    )
    (net (code "56") (name "unconnected-(U3-NC5-PadG2)") (class "Default")
      (node (ref "U3") (pin "G2") (pinfunction "NC5_G2") (pintype "passive"))
    )
    (net (code "57") (name "unconnected-(U3-NC6-PadH3)") (class "Default")
      (node (ref "U3") (pin "H3") (pinfunction "NC6_H3") (pintype "passive"))
    )
    (net (code "58") (name "unconnected-(U3-NC7-PadJ3)") (class "Default")
      (node (ref "U3") (pin "J3") (pinfunction "NC7_J3") (pintype "passive"))
    )
    (net (code "59") (name "unconnected-(U3-NC8-PadC9)") (class "Default")
      (node (ref "U3") (pin "C9") (pinfunction "NC8_C9") (pintype "passive"))
    )
    (net (code "60") (name "unconnected-(U3-NC9-PadD9)") (class "Default")
      (node (ref "U3") (pin "D9") (pinfunction "NC9_D9") (pintype "passive"))
    )
    (net (code "61") (name "unconnected-(U3-NC10-PadE9)") (class "Default")
      (node (ref "U3") (pin "E9") (pinfunction "NC10_E9") (pintype "passive"))
    )
    (net (code "62") (name "unconnected-(U3-NC11-PadF9)") (class "Default")
      (node (ref "U3") (pin "F9") (pinfunction "NC11_F9") (pintype "passive"))
    )
    (net (code "63") (name "unconnected-(U3-NC12-PadC10)") (class "Default")
      (node (ref "U3") (pin "C10") (pinfunction "NC12_C10") (pintype "passive"))
    )
    (net (code "64") (name "unconnected-(U3-NC13-PadD10)") (class "Default")
      (node (ref "U3") (pin "D10") (pinfunction "NC13_D10") (pintype "passive"))
    )
    (net (code "65") (name "unconnected-(U3-NC14-PadE10)") (class "Default")
      (node (ref "U3") (pin "E10") (pinfunction "NC14_E10") (pintype "passive"))
    )
    (net (code "66") (name "unconnected-(U3-NC15-PadF10)") (class "Default")
      (node (ref "U3") (pin "F10") (pinfunction "NC15_F10") (pintype "passive"))
    )
    (net (code "67") (name "unconnected-(U3-SCK-PadA4)") (class "Default")
      (node (ref "U3") (pin "A4") (pinfunction "SCK_A4") (pintype "passive"))
    )
    (net (code "68") (name "unconnected-(U3-SCSB-PadB4)") (class "Default")
      (node (ref "U3") (pin "B4") (pinfunction "SCSB_B4") (pintype "passive"))
    )
    (net (code "69") (name "unconnected-(U3-SDO-PadB5)") (class "Default")
      (node (ref "U3") (pin "B5") (pinfunction "SDO_B5") (pintype "passive"))
    )
    (net (code "70") (name "unconnected-(U3-SWDIO-PadH9)") (class "Default")
      (node (ref "U3") (pin "H9") (pinfunction "SWDIO_H9") (pintype "passive"))
    )
    (net (code "71") (name "unconnected-(U3-SWTCK-PadH10)") (class "Default")
      (node (ref "U3") (pin "H10") (pinfunction "SWTCK_H10") (pintype "passive"))
    )
    (net (code "72") (name "unconnected-(U3-TENABLE-PadB8)") (class "Default")
      (node (ref "U3") (pin "B8") (pinfunction "TENABLE_B8") (pintype "passive"))
    )
    (net (code "73") (name "unconnected-(U3-TVCDSIN-PadG3)") (class "Default")
      (node (ref "U3") (pin "G3") (pinfunction "TVCDSIN_G3") (pintype "passive"))
    )
    (net (code "74") (name "unconnected-(U3-TVMON-PadF3)") (class "Default")
      (node (ref "U3") (pin "F3") (pinfunction "TVMON_F3") (pintype "passive"))
    )
  )
)
